# USB.net
KiCad netlist of a schematic drawn in Altium Designer
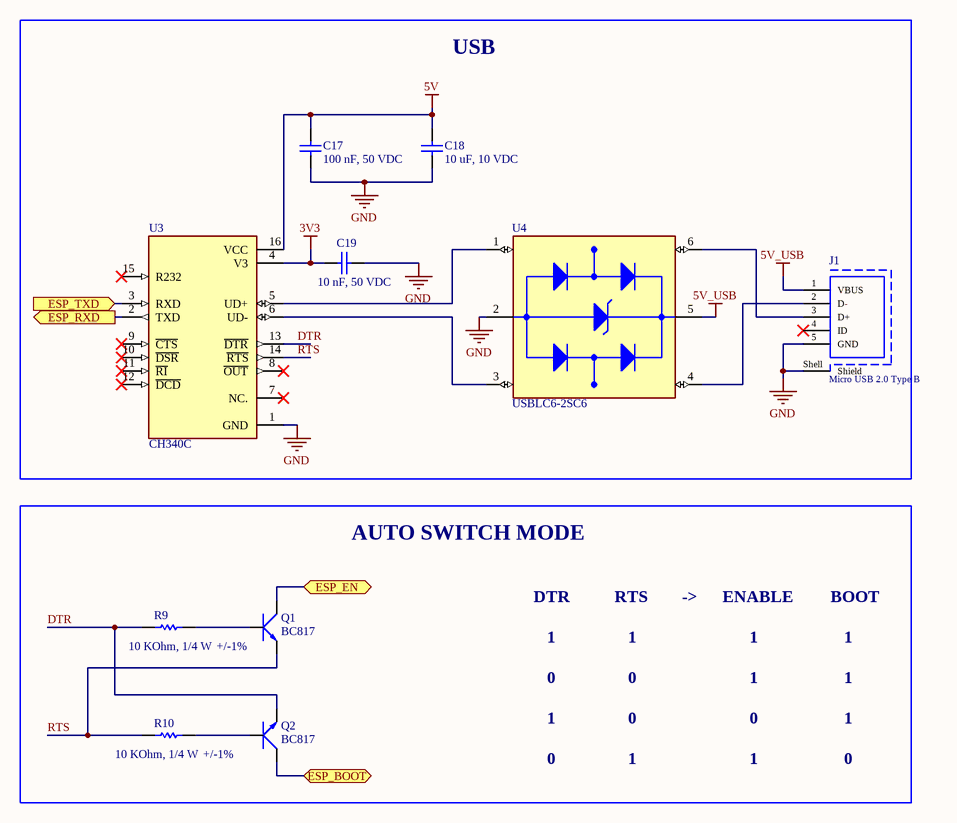
[diagram p0: USB.SchDoc]

(export (version "E")
  (design (tool "Eeschema 10.0.6"))
  (components
    (comp (ref "C17")
      (value "100 nF, 50 VDC")
      (footprint "CAP_0603")
      (description "CAP, size 0603, 100 nF, 50 VDC")
      (fields (field (name "TOLERANCE") "+/-10%"))
      (libsource (lib "Altium_Ceramic_Cap") (part "0106031041050"))
    )
    (comp (ref "C18")
      (value "10 uF, 10 VDC")
      (footprint "CAP_0603")
      (description "CAP, size 0603, 10 uF, 10 VDC")
      (fields (field (name "TOLERANCE") "+/-10%"))
      (libsource (lib "Altium_Ceramic_Cap") (part "0106031061010"))
    )
    (comp (ref "C19")
      (value "10 nF, 50 VDC")
      (footprint "CAP_0603")
      (description "CAP, size 0603, 10 nF, 50 VDC")
      (fields (field (name "TOLERANCE") "+/-10%"))
      (libsource (lib "Altium_Ceramic_Cap") (part "0106031031050"))
    )
    (comp (ref "J1")
      (value "Micro USB 2.0 Type B")
      (footprint "629105150521")
      (description "Micro USB 2.0 Type B Receptacle WR-COM, Horizontal, SMT, with Pegs, High Current at Pin 1 & Pin 5")
      (fields (field (name "PART NUMBER") "629105150521") (field (name "PUBLISHER") "Wurth Elektronik"))
      (libsource (lib "Altium_USB") (part "629105150521"))
    )
    (comp (ref "Q1")
      (value "BC817")
      (footprint "SOT-23")
      (description "SOT-23 - C8658")
      (libsource (lib "TranFet") (part "Trans BC817"))
    )
    (comp (ref "Q2")
      (value "BC817")
      (footprint "SOT-23")
      (description "SOT-23 - C8658")
      (libsource (lib "TranFet") (part "Trans BC817"))
    )
    (comp (ref "R9")
      (value "10 KOhm, 1/4 W")
      (footprint "resistor_0603")
      (description "RES, size 0603, 10 KOhm, 1/4 W")
      (fields (field (name "RESISTANCE TOLERANCE") "+/-1%"))
      (libsource (lib "Altium_Resistor") (part "0006031031"))
    )
    (comp (ref "R10")
      (value "10 KOhm, 1/4 W")
      (footprint "resistor_0603")
      (description "RES, size 0603, 10 KOhm, 1/4 W")
      (fields (field (name "RESISTANCE TOLERANCE") "+/-1%"))
      (libsource (lib "Altium_Resistor") (part "0006031031"))
    )
    (comp (ref "U3")
      (value "CH340C")
      (footprint "SOIC127P600X180-16N")
      (description "USB to serial chip CH340")
      (fields (field (name "MF") "WCH"))
      (libsource (lib "CH340C") (part "CH340C"))
    )
    (comp (ref "U4")
      (value "USBLC6-2SC6")
      (footprint "SOT95P280X145-6N")
      (description "17V Clamp 5A (8/20Âµs) Ipp Tvs Diode Surface Mount SOT-23-6")
      (fields (field (name "MF") "STMicroelectronics"))
      (libsource (lib "USBLC6-2SC6") (part "USBLC6-2SC6"))
    )
  )
  (nets
    (net (code "1") (name "/DTR") (class "Default")
      (node (ref "Q2") (pin "2") (pinfunction "E_2") (pintype "passive"))
      (node (ref "R9") (pin "1") (pinfunction "1_1") (pintype "passive"))
      (node (ref "U3") (pin "13") (pinfunction "~{DTR}_13") (pintype "output"))
    )
    (net (code "2") (name "/ESP_BOOT") (class "Default")
      (node (ref "Q2") (pin "3") (pinfunction "C_3") (pintype "passive"))
    )
    (net (code "3") (name "/ESP_EN") (class "Default")
      (node (ref "Q1") (pin "3") (pinfunction "C_3") (pintype "passive"))
    )
    (net (code "4") (name "/ESP_RXD") (class "Default")
      (node (ref "U3") (pin "2") (pinfunction "TXD_2") (pintype "output"))
    )
    (net (code "5") (name "/ESP_TXD") (class "Default")
      (node (ref "U3") (pin "3") (pinfunction "RXD_3") (pintype "input"))
    )
    (net (code "6") (name "/RTS") (class "Default")
      (node (ref "Q1") (pin "2") (pinfunction "E_2") (pintype "passive"))
      (node (ref "R10") (pin "1") (pinfunction "1_1") (pintype "passive"))
      (node (ref "U3") (pin "14") (pinfunction "~{RTS}_14") (pintype "output"))
    )
    (net (code "7") (name "3V3") (class "Default")
      (node (ref "C19") (pin "1") (pinfunction "1_1") (pintype "passive"))
      (node (ref "U3") (pin "4") (pinfunction "V3_4") (pintype "power_in"))
    )
    (net (code "8") (name "5V") (class "Default")
      (node (ref "C17") (pin "2") (pinfunction "2_2") (pintype "passive"))
      (node (ref "C18") (pin "2") (pinfunction "2_2") (pintype "passive"))
      (node (ref "U3") (pin "16") (pinfunction "VCC_16") (pintype "power_in"))
    )
    (net (code "9") (name "5V_USB") (class "Default")
      (node (ref "J1") (pin "1") (pinfunction "VBUS_1") (pintype "passive"))
      (node (ref "U4") (pin "5") (pinfunction "VBUS_5") (pintype "power_in"))
    )
    (net (code "10") (name "GND") (class "Default")
      (node (ref "C17") (pin "1") (pinfunction "1_1") (pintype "passive"))
      (node (ref "C18") (pin "1") (pinfunction "1_1") (pintype "passive"))
      (node (ref "C19") (pin "2") (pinfunction "2_2") (pintype "passive"))
      (node (ref "J1") (pin "5") (pinfunction "GND_5") (pintype "passive"))
      (node (ref "J1") (pin "Shell") (pinfunction "Shield_Shell") (pintype "passive"))
      (node (ref "U3") (pin "1") (pinfunction "GND_1") (pintype "power_in"))
      (node (ref "U4") (pin "2") (pinfunction "GND_2") (pintype "power_in"))
    )
    (net (code "11") (name "Net-(J1-D+)") (class "Default")
      (node (ref "J1") (pin "3") (pinfunction "D+_3") (pintype "passive"))
      (node (ref "U4") (pin "6") (pinfunction "I/O1_OUT_6") (pintype "bidirectional"))
    )
    (net (code "12") (name "Net-(J1-D-)") (class "Default")
      (node (ref "J1") (pin "2") (pinfunction "D-_2") (pintype "passive"))
      (node (ref "U4") (pin "4") (pinfunction "I/O2_OUT_4") (pintype "bidirectional"))
    )
    (net (code "13") (name "Net-(Q1-B)") (class "Default")
      (node (ref "Q1") (pin "1") (pinfunction "B_1") (pintype "passive"))
      (node (ref "R9") (pin "2") (pinfunction "2_2") (pintype "passive"))
    )
    (net (code "14") (name "Net-(Q2-B)") (class "Default")
      (node (ref "Q2") (pin "1") (pinfunction "B_1") (pintype "passive"))
      (node (ref "R10") (pin "2") (pinfunction "2_2") (pintype "passive"))
    )
    (net (code "15") (name "Net-(U3-UD+)") (class "Default")
      (node (ref "U3") (pin "5") (pinfunction "UD+_5") (pintype "bidirectional"))
      (node (ref "U4") (pin "1") (pinfunction "I/O1_IN_1") (pintype "bidirectional"))
    )
    (net (code "16") (name "Net-(U3-UD-)") (class "Default")
      (node (ref "U3") (pin "6") (pinfunction "UD-_6") (pintype "bidirectional"))
      (node (ref "U4") (pin "3") (pinfunction "I/O2_IN_3") (pintype "bidirectional"))
    )
    (net (code "17") (name "unconnected-(J1-ID-Pad4)") (class "Default")
      (node (ref "J1") (pin "4") (pinfunction "ID_4") (pintype "passive+no_connect"))
    )
    (net (code "18") (name "unconnected-(U3-NC.-Pad7)") (class "Default")
      (node (ref "U3") (pin "7") (pinfunction "NC._7") (pintype "passive+no_connect"))
    )
    (net (code "19") (name "unconnected-(U3-R232-Pad15)") (class "Default")
      (node (ref "U3") (pin "15") (pinfunction "R232_15") (pintype "input+no_connect"))
    )
    (net (code "20") (name "unconnected-(U3-~{CTS}-Pad9)") (class "Default")
      (node (ref "U3") (pin "9") (pinfunction "~{CTS}_9") (pintype "input+no_connect"))
    )
    (net (code "21") (name "unconnected-(U3-~{DCD}-Pad12)") (class "Default")
      (node (ref "U3") (pin "12") (pinfunction "~{DCD}_12") (pintype "input+no_connect"))
    )
    (net (code "22") (name "unconnected-(U3-~{DSR}-Pad10)") (class "Default")
      (node (ref "U3") (pin "10") (pinfunction "~{DSR}_10") (pintype "input+no_connect"))
    )
    (net (code "23") (name "unconnected-(U3-~{OUT}-Pad8)") (class "Default")
      (node (ref "U3") (pin "8") (pinfunction "~{OUT}_8") (pintype "output+no_connect"))
    )
    (net (code "24") (name "unconnected-(U3-~{RI}-Pad11)") (class "Default")
      (node (ref "U3") (pin "11") (pinfunction "~{RI}_11") (pintype "input+no_connect"))
    )
  )
)
